# reefpi_pico_smc.net
KiCad netlist of a schematic drawn in Altium Designer
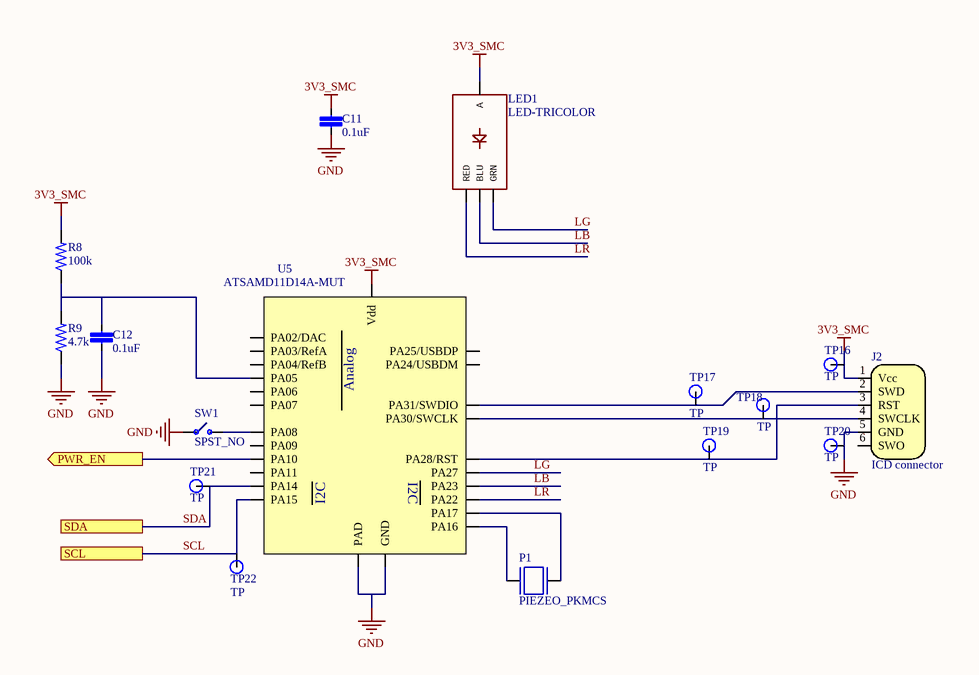
[diagram p0: reefpi_pico_smc.SchDoc]

(export (version "E")
  (design (tool "Eeschema 10.0.6"))
  (components
    (comp (ref "C11") (value "0.1uF") (footprint "C0603") (libsource (lib "rcl") (part "C-EU")))
    (comp (ref "C12") (value "0.1uF") (footprint "C0603") (libsource (lib "rcl") (part "C-EU")))
    (comp (ref "J2")
      (value "ICD connector")
      (footprint "TC2030-MCP-NL")
      (description "Conector par ICD")
      (libsource (lib "TC2030") (part "TC2030-SWD-NL"))
    )
    (comp (ref "LED1")
      (value "LED-TRICOLOR")
      (footprint "LED-TRICOLOR-SMD")
      (libsource (lib "led") (part "LED-TRICOLOR"))
    )
    (comp (ref "P1")
      (value "PIEZEO_PKMCS")
      (footprint "PIEZO_PKMCS0909E4000")
      (libsource (lib "murata") (part "PIEZEO_PKMCS"))
    )
    (comp (ref "R8") (value "100k") (footprint "R0603") (libsource (lib "rcl") (part "R-US")))
    (comp (ref "R9") (value "4.7k") (footprint "R0603") (libsource (lib "rcl") (part "R-US")))
    (comp (ref "SW1") (value "SPST_NO") (footprint "B3U-1000P") (libsource (lib "switches") (part "SPST_NO")))
    (comp (ref "TP16") (value "TP") (footprint "TP_0.89mm") (libsource (lib "testpoints") (part "TP")))
    (comp (ref "TP17") (value "TP") (footprint "TP_0.89mm") (libsource (lib "testpoints") (part "TP")))
    (comp (ref "TP18") (value "TP") (footprint "TP_0.89mm") (libsource (lib "testpoints") (part "TP")))
    (comp (ref "TP19") (value "TP") (footprint "TP_0.89mm") (libsource (lib "testpoints") (part "TP")))
    (comp (ref "TP20") (value "TP") (footprint "TP_0.89mm") (libsource (lib "testpoints") (part "TP")))
    (comp (ref "TP21") (value "TP") (footprint "TP_0.89mm") (libsource (lib "testpoints") (part "TP")))
    (comp (ref "TP22") (value "TP") (footprint "TP_0.89mm") (libsource (lib "testpoints") (part "TP")))
    (comp (ref "U5")
      (value "ATSAMD11D14A-MUT")
      (footprint "QFN24-4x4mm-0.5")
      (libsource (lib "atmel") (part "ATSAMD11D14A-MUT"))
    )
  )
  (nets
    (net (code "1") (name "/LB") (class "Default")
      (node (ref "LED1") (pin "B") (pinfunction "BLU_B") (pintype "passive"))
      (node (ref "U5") (pin "16") (pinfunction "PA23_16") (pintype "passive"))
    )
    (net (code "2") (name "/LG") (class "Default")
      (node (ref "LED1") (pin "G") (pinfunction "GRN_G") (pintype "passive"))
      (node (ref "U5") (pin "17") (pinfunction "PA27_17") (pintype "passive"))
    )
    (net (code "3") (name "/LR") (class "Default")
      (node (ref "LED1") (pin "R") (pinfunction "RED_R") (pintype "passive"))
      (node (ref "U5") (pin "15") (pinfunction "PA22_15") (pintype "passive"))
    )
    (net (code "4") (name "/PWR_EN") (class "Default")
      (node (ref "U5") (pin "9") (pinfunction "PA10_9") (pintype "passive"))
    )
    (net (code "5") (name "/SCL") (class "Default")
      (node (ref "TP22") (pin "1") (pinfunction "1_1") (pintype "passive"))
      (node (ref "U5") (pin "12") (pinfunction "PA15_12") (pintype "passive"))
    )
    (net (code "6") (name "/SDA") (class "Default")
      (node (ref "TP21") (pin "1") (pinfunction "1_1") (pintype "passive"))
      (node (ref "U5") (pin "11") (pinfunction "PA14_11") (pintype "passive"))
    )
    (net (code "7") (name "3V3_SMC") (class "Default")
      (node (ref "C11") (pin "1") (pinfunction "1_1") (pintype "passive"))
      (node (ref "J2") (pin "1") (pinfunction "Vcc_1") (pintype "passive"))
      (node (ref "LED1") (pin "A") (pinfunction "A_A") (pintype "passive"))
      (node (ref "R8") (pin "2") (pinfunction "2_2") (pintype "passive"))
      (node (ref "TP16") (pin "1") (pinfunction "1_1") (pintype "passive"))
      (node (ref "U5") (pin "24") (pinfunction "Vdd_24") (pintype "power_in"))
    )
    (net (code "8") (name "GND") (class "Default")
      (node (ref "C11") (pin "2") (pinfunction "2_2") (pintype "passive"))
      (node (ref "C12") (pin "2") (pinfunction "2_2") (pintype "passive"))
      (node (ref "J2") (pin "5") (pinfunction "GND_5") (pintype "passive"))
      (node (ref "R9") (pin "1") (pinfunction "1_1") (pintype "passive"))
      (node (ref "SW1") (pin "2") (pinfunction "2_2") (pintype "passive"))
      (node (ref "TP20") (pin "1") (pinfunction "1_1") (pintype "passive"))
      (node (ref "U5") (pin "23") (pinfunction "GND_23") (pintype "power_in"))
      (node (ref "U5") (pin "PAD") (pinfunction "PAD_PAD") (pintype "power_in"))
    )
    (net (code "9") (name "Net-(J2-RST)") (class "Default")
      (node (ref "J2") (pin "3") (pinfunction "RST_3") (pintype "passive"))
      (node (ref "TP19") (pin "1") (pinfunction "1_1") (pintype "passive"))
      (node (ref "U5") (pin "18") (pinfunction "PA28/RST_18") (pintype "passive"))
    )
    (net (code "10") (name "Net-(J2-SWCLK)") (class "Default")
      (node (ref "J2") (pin "4") (pinfunction "SWCLK_4") (pintype "passive"))
      (node (ref "TP18") (pin "1") (pinfunction "1_1") (pintype "passive"))
      (node (ref "U5") (pin "19") (pinfunction "PA30/SWCLK_19") (pintype "passive"))
    )
    (net (code "11") (name "Net-(J2-SWD)") (class "Default")
      (node (ref "J2") (pin "2") (pinfunction "SWD_2") (pintype "passive"))
      (node (ref "TP17") (pin "1") (pinfunction "1_1") (pintype "passive"))
      (node (ref "U5") (pin "20") (pinfunction "PA31/SWDIO_20") (pintype "passive"))
    )
    (net (code "12") (name "Net-(U5-PA05)") (class "Default")
      (node (ref "C12") (pin "1") (pinfunction "1_1") (pintype "passive"))
      (node (ref "R8") (pin "1") (pinfunction "1_1") (pintype "passive"))
      (node (ref "R9") (pin "2") (pinfunction "2_2") (pintype "passive"))
      (node (ref "U5") (pin "4") (pinfunction "PA05_4") (pintype "passive"))
    )
    (net (code "13") (name "Net-(U5-PA08)") (class "Default")
      (node (ref "SW1") (pin "1") (pinfunction "1_1") (pintype "passive"))
      (node (ref "U5") (pin "7") (pinfunction "PA08_7") (pintype "passive"))
    )
    (net (code "14") (name "Net-(U5-PA16)") (class "Default")
      (node (ref "P1") (pin "2") (pinfunction "2_2") (pintype "passive"))
      (node (ref "U5") (pin "13") (pinfunction "PA16_13") (pintype "passive"))
    )
    (net (code "15") (name "Net-(U5-PA17)") (class "Default")
      (node (ref "P1") (pin "1") (pinfunction "1_1") (pintype "passive"))
      (node (ref "U5") (pin "14") (pinfunction "PA17_14") (pintype "passive"))
    )
    (net (code "16") (name "unconnected-(J2-SWO-Pad6)") (class "Default")
      (node (ref "J2") (pin "6") (pinfunction "SWO_6") (pintype "passive"))
    )
    (net (code "17") (name "unconnected-(U5-PA02{slash}DAC-Pad1)") (class "Default")
      (node (ref "U5") (pin "1") (pinfunction "PA02/DAC_1") (pintype "passive"))
    )
    (net (code "18") (name "unconnected-(U5-PA03{slash}RefA-Pad2)") (class "Default")
      (node (ref "U5") (pin "2") (pinfunction "PA03/RefA_2") (pintype "passive"))
    )
    (net (code "19") (name "unconnected-(U5-PA04{slash}RefB-Pad3)") (class "Default")
      (node (ref "U5") (pin "3") (pinfunction "PA04/RefB_3") (pintype "passive"))
    )
    (net (code "20") (name "unconnected-(U5-PA06-Pad5)") (class "Default")
      (node (ref "U5") (pin "5") (pinfunction "PA06_5") (pintype "passive"))
    )
    (net (code "21") (name "unconnected-(U5-PA07-Pad6)") (class "Default")
      (node (ref "U5") (pin "6") (pinfunction "PA07_6") (pintype "passive"))
    )
    (net (code "22") (name "unconnected-(U5-PA09-Pad8)") (class "Default")
      (node (ref "U5") (pin "8") (pinfunction "PA09_8") (pintype "passive"))
    )
    (net (code "23") (name "unconnected-(U5-PA11-Pad10)") (class "Default")
      (node (ref "U5") (pin "10") (pinfunction "PA11_10") (pintype "passive"))
    )
    (net (code "24") (name "unconnected-(U5-PA24{slash}USBDM-Pad21)") (class "Default")
      (node (ref "U5") (pin "21") (pinfunction "PA24/USBDM_21") (pintype "passive"))
    )
    (net (code "25") (name "unconnected-(U5-PA25{slash}USBDP-Pad22)") (class "Default")
      (node (ref "U5") (pin "22") (pinfunction "PA25/USBDP_22") (pintype "passive"))
    )
  )
)
